# TDA7292_Amplifier.net
KiCad netlist of a schematic drawn in Altium Designer
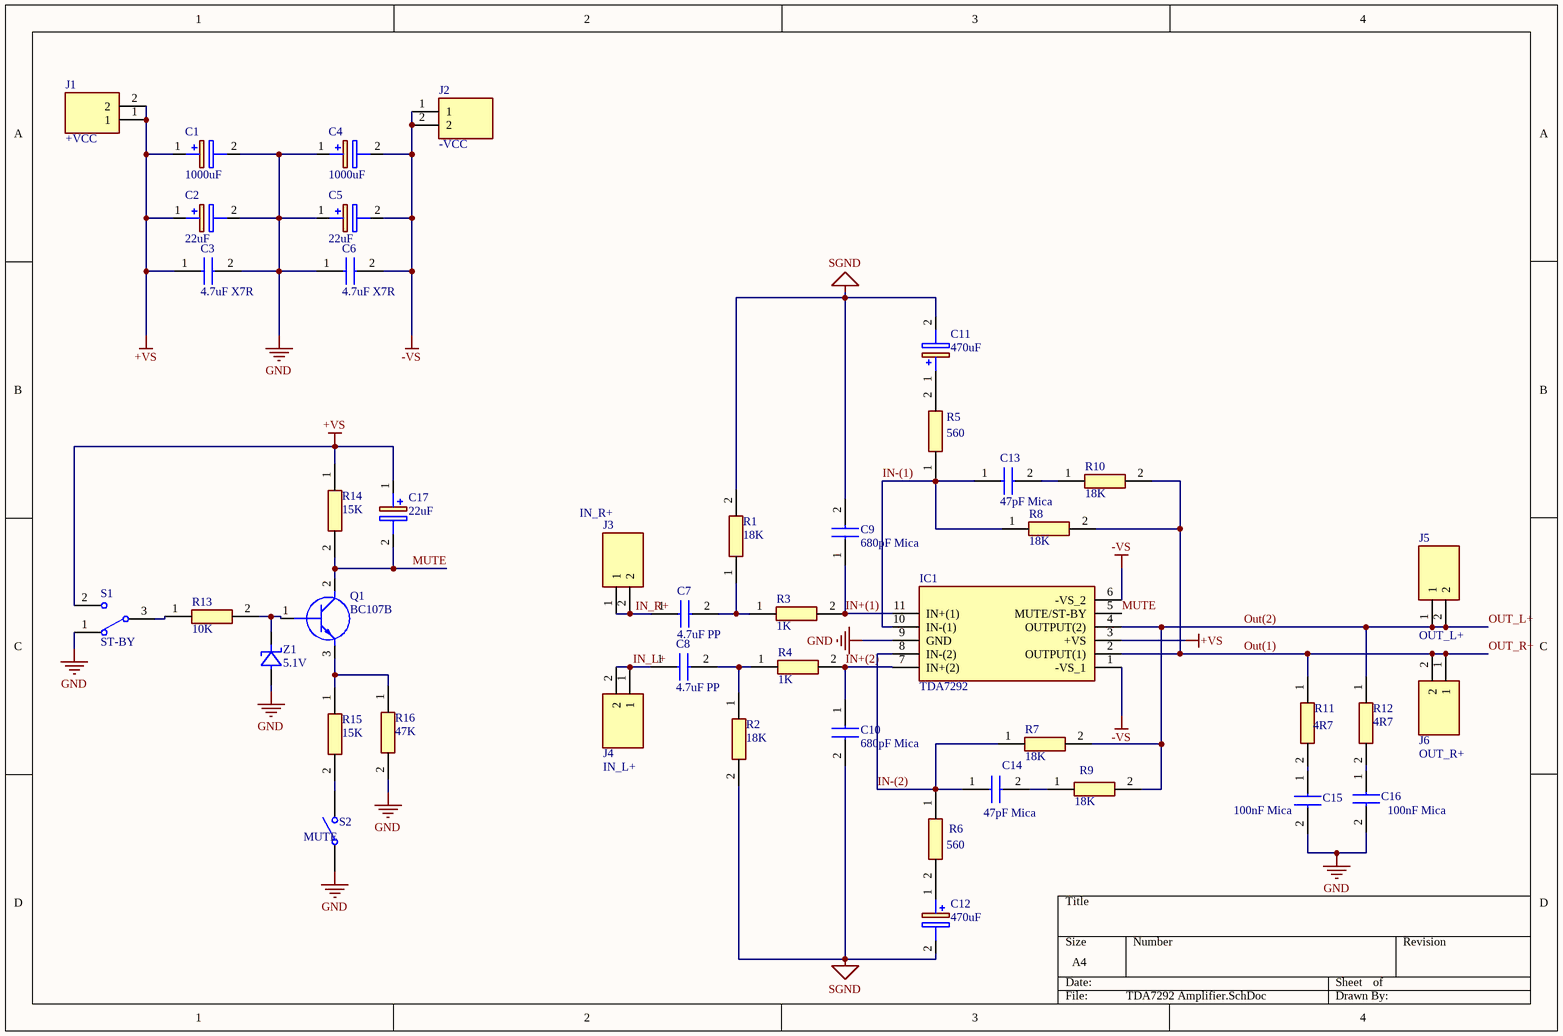
[diagram p0: TDA7292 Amplifier.SchDoc]

(export (version "E")
  (design (tool "Eeschema 10.0.6"))
  (components
    (comp (ref "C1")
      (value "1000uF")
      (footprint "Capacitor 1000uF")
      (description "Electroletic Capacitor Polarised")
      (fields
        (field (name "MANUFACTURER_PART_NUMBER") "UHE1H102MHD6TN")
        (field (name "MOUSER PART NUMBER") "647-UHE1H102MHD6TN")
      )
      (libsource (lib "TDA7292 Amplifier") (part "1000uF"))
    )
    (comp (ref "C2")
      (value "22uF")
      (footprint "Capacitor 22uF")
      (description "Electroletic Capacitor Polarised")
      (fields
        (field (name "MANUFACTURER_PART_NUMBER") "EEU-FM1H220")
        (field (name "MOUSER PART NUMBER") "667-EEU-FM1H220")
      )
      (libsource (lib "") (part "22uF_1"))
    )
    (comp (ref "C3")
      (value "4.7uF X7R")
      (footprint "Capacitor 4.7UF 50V X7R")
      (description "Capacitor 4.7UF 50V X7R")
      (fields
        (field (name "MANUFACTURER_PART_NUMBER") "RCER71H475K3M1H03A")
        (field (name "MOUSER PART NUMBER") "81-RCER71H475K3M1H3A")
      )
      (libsource (lib "TDA7292 Amplifier") (part "4.7uF X7R"))
    )
    (comp (ref "C4")
      (value "1000uF")
      (footprint "Capacitor 1000uF")
      (description "Electroletic Capacitor Polarised")
      (fields
        (field (name "MANUFACTURER_PART_NUMBER") "UHE1H102MHD6TN")
        (field (name "MOUSER PART NUMBER") "647-UHE1H102MHD6TN")
      )
      (libsource (lib "TDA7292 Amplifier") (part "1000uF"))
    )
    (comp (ref "C5")
      (value "22uF")
      (footprint "Capacitor 22uF")
      (description "Electroletic Capacitor Polarised")
      (fields
        (field (name "MANUFACTURER_PART_NUMBER") "EEU-FM1H220")
        (field (name "MOUSER PART NUMBER") "667-EEU-FM1H220")
      )
      (libsource (lib "") (part "22uF_1"))
    )
    (comp (ref "C6")
      (value "4.7uF X7R")
      (footprint "Capacitor 4.7UF 50V X7R")
      (description "Capacitor 4.7UF 50V X7R")
      (fields
        (field (name "MANUFACTURER_PART_NUMBER") "RCER71H475K3M1H03A")
        (field (name "MOUSER PART NUMBER") "81-RCER71H475K3M1H3A")
      )
      (libsource (lib "TDA7292 Amplifier") (part "4.7uF X7R"))
    )
    (comp (ref "C7")
      (value "4.7uF PP")
      (footprint "4.7UF Polypropylene")
      (description "Cap Film 4.7uF 450VDC PP 5% (25.3 X 11.7 X 16.4mm) Radial 22.5mm 110C Bulk")
      (fields
        (field (name "MANUFACTURER") "Panasonic")
        (field (name "MANUFACTURER PART NUMBER") "ECW-FD2W475J")
      )
      (libsource (lib "TDA7292 Amplifier") (part "4.7uF PP"))
    )
    (comp (ref "C8")
      (value "4.7uF PP")
      (footprint "4.7UF Polypropylene")
      (description "Cap Film 4.7uF 450VDC PP 5% (25.3 X 11.7 X 16.4mm) Radial 22.5mm 110C Bulk")
      (fields
        (field (name "MANUFACTURER") "Panasonic")
        (field (name "MANUFACTURER PART NUMBER") "ECW-FD2W475J")
      )
      (libsource (lib "TDA7292 Amplifier") (part "4.7uF PP"))
    )
    (comp (ref "C9")
      (value "680pF Mica")
      (footprint "680pF Mica")
      (description "Capacitor 680pF Mica")
      (fields
        (field (name "MANUFACTURER_PART_NUMBER") "CD15FD221FO3F")
        (field (name "MOUSER PART NUMBER") "598-CD15FD221FO3F")
      )
      (libsource (lib "TDA7292 Amplifier") (part "680pF Mica"))
    )
    (comp (ref "C10")
      (value "680pF Mica")
      (footprint "680pF Mica")
      (description "Capacitor 680pF Mica")
      (fields
        (field (name "MANUFACTURER_PART_NUMBER") "CD15FD221FO3F")
        (field (name "MOUSER PART NUMBER") "598-CD15FD221FO3F")
      )
      (libsource (lib "TDA7292 Amplifier") (part "680pF Mica"))
    )
    (comp (ref "C11")
      (value "470uF")
      (footprint "Capacitor 470uF")
      (description "Electroletic Capacitor Polarised")
      (fields
        (field (name "MANUFACTURER_PART_NUMBER") "EEUFM1H471")
        (field (name "RS PART NUMBER") "5261698P")
      )
      (libsource (lib "TDA7292 Amplifier") (part "470uF"))
    )
    (comp (ref "C12")
      (value "470uF")
      (footprint "Capacitor 470uF")
      (description "Electroletic Capacitor Polarised")
      (fields
        (field (name "MANUFACTURER_PART_NUMBER") "EEUFM1H471")
        (field (name "RS PART NUMBER") "5261698P")
      )
      (libsource (lib "") (part "470uF_1"))
    )
    (comp (ref "C13")
      (value "47pF Mica")
      (footprint "47pF Mica")
      (description "Capacitor 47pF Mica")
      (fields
        (field (name "MANUFACTURER_PART_NUMBER") "CD15FD221FO3F")
        (field (name "MOUSER PART NUMBER") "598-CD15FD221FO3F")
      )
      (libsource (lib "TDA7292 Amplifier") (part "47pF Mica"))
    )
    (comp (ref "C14")
      (value "47pF Mica")
      (footprint "47pF Mica")
      (description "Capacitor 47pF Mica")
      (fields
        (field (name "MANUFACTURER_PART_NUMBER") "CD15FD221FO3F")
        (field (name "MOUSER PART NUMBER") "598-CD15FD221FO3F")
      )
      (libsource (lib "TDA7292 Amplifier") (part "47pF Mica"))
    )
    (comp (ref "C15")
      (value "100nF Mica")
      (footprint "680pF Mica")
      (description "Capacitor 680pF Mica")
      (fields
        (field (name "MANUFACTURER_PART_NUMBER") "CD15FD221FO3F")
        (field (name "MOUSER PART NUMBER") "598-CD15FD221FO3F")
      )
      (libsource (lib "TDA7292 Amplifier") (part "680pF Mica"))
    )
    (comp (ref "C16")
      (value "100nF Mica")
      (footprint "680pF Mica")
      (description "Capacitor 680pF Mica")
      (fields
        (field (name "MANUFACTURER_PART_NUMBER") "CD15FD221FO3F")
        (field (name "MOUSER PART NUMBER") "598-CD15FD221FO3F")
      )
      (libsource (lib "TDA7292 Amplifier") (part "680pF Mica"))
    )
    (comp (ref "C17")
      (value "22uF")
      (footprint "Capacitor 22uF")
      (description "Electroletic Capacitor Polarised")
      (fields
        (field (name "MANUFACTURER_PART_NUMBER") "EEU-FM1H220")
        (field (name "MOUSER PART NUMBER") "667-EEU-FM1H220")
      )
      (libsource (lib "TDA7292 Amplifier") (part "22uF"))
    )
    (comp (ref "IC1")
      (value "TDA7292")
      (footprint "TDA7292")
      (description "Integrated Circuit")
      (fields (field (name "MOUSER PART NUMBER") "511-TDA7292"))
      (libsource (lib "TDA7292 Amplifier") (part "TDA7292"))
    )
    (comp (ref "J1")
      (value "+VCC")
      (footprint "Spade Terminals")
      (description "Connector")
      (fields
        (field (name "MANUFACTURER_PART_NUMBER") "725964-2")
        (field (name "MOUSER PART NUMBER") "571-725964-2")
      )
      (libsource (lib "") (part "Spade Terminals_1"))
    )
    (comp (ref "J2")
      (value "-VCC")
      (footprint "Spade Terminals")
      (description "Connector")
      (fields
        (field (name "MANUFACTURER_PART_NUMBER") "725964-2")
        (field (name "MOUSER PART NUMBER") "571-725964-2")
      )
      (libsource (lib "") (part "Spade Terminals_3"))
    )
    (comp (ref "J3")
      (value "IN_R+")
      (footprint "Spade Terminals")
      (description "Connector")
      (fields
        (field (name "MANUFACTURER_PART_NUMBER") "725964-2")
        (field (name "MOUSER PART NUMBER") "571-725964-2")
      )
      (libsource (lib "") (part "Spade Terminals_2"))
    )
    (comp (ref "J4")
      (value "IN_L+")
      (footprint "Spade Terminals")
      (description "Connector")
      (fields
        (field (name "MANUFACTURER_PART_NUMBER") "725964-2")
        (field (name "MOUSER PART NUMBER") "571-725964-2")
      )
      (libsource (lib "TDA7292 Amplifier") (part "Spade Terminals"))
    )
    (comp (ref "J5")
      (value "OUT_L+")
      (footprint "Spade Terminals")
      (description "Connector")
      (fields
        (field (name "MANUFACTURER_PART_NUMBER") "725964-2")
        (field (name "MOUSER PART NUMBER") "571-725964-2")
      )
      (libsource (lib "") (part "Spade Terminals_2"))
    )
    (comp (ref "J6")
      (value "OUT_R+")
      (footprint "Spade Terminals")
      (description "Connector")
      (fields
        (field (name "MANUFACTURER_PART_NUMBER") "725964-2")
        (field (name "MOUSER PART NUMBER") "571-725964-2")
      )
      (libsource (lib "TDA7292 Amplifier") (part "Spade Terminals"))
    )
    (comp (ref "Q1")
      (value "BC107B")
      (footprint "TDA7292 Amplifier:TO-18")
      (description "Transistor BJT NPN")
      (fields (field (name "MOUSER PART NUMBER") "511-BC107B") (field (name "RS PART NUMBER") "7140489P"))
      (libsource (lib "TDA7292 Amplifier") (part "BC107B"))
    )
    (comp (ref "R1")
      (value "18K")
      (footprint "RES 1/4W")
      (description "Resistor")
      (fields
        (field (name "MANUFACTURER_PART_NUMBER") "CFR-25JT-52-1K")
        (field (name "MOUSER PART NUMBER") "603-CFR-25JT-52-1K")
      )
      (libsource (lib "") (part "Resistor 1/4W_2"))
    )
    (comp (ref "R2")
      (value "18K")
      (footprint "RES 1/4W")
      (description "Resistor")
      (fields
        (field (name "MANUFACTURER_PART_NUMBER") "CFR-25JT-52-1K")
        (field (name "MOUSER PART NUMBER") "603-CFR-25JT-52-1K")
      )
      (libsource (lib "") (part "Resistor 1/4W_1"))
    )
    (comp (ref "R3")
      (value "1K")
      (footprint "RES 1/4W")
      (description "Resistor")
      (fields
        (field (name "MANUFACTURER_PART_NUMBER") "CFR-25JT-52-1K")
        (field (name "MOUSER PART NUMBER") "603-CFR-25JT-52-1K")
      )
      (libsource (lib "TDA7292 Amplifier") (part "Resistor 1/4W"))
    )
    (comp (ref "R4")
      (value "1K")
      (footprint "RES 1/4W")
      (description "Resistor")
      (fields
        (field (name "MANUFACTURER_PART_NUMBER") "CFR-25JT-52-1K")
        (field (name "MOUSER PART NUMBER") "603-CFR-25JT-52-1K")
      )
      (libsource (lib "TDA7292 Amplifier") (part "Resistor 1/4W"))
    )
    (comp (ref "R5")
      (value "560")
      (footprint "RES 1/4W")
      (description "Resistor")
      (fields
        (field (name "MANUFACTURER_PART_NUMBER") "CFR-25JT-52-1K")
        (field (name "MOUSER PART NUMBER") "603-CFR-25JT-52-1K")
      )
      (libsource (lib "") (part "Resistor 1/4W_2"))
    )
    (comp (ref "R6")
      (value "560")
      (footprint "RES 1/4W")
      (description "Resistor")
      (fields
        (field (name "MANUFACTURER_PART_NUMBER") "CFR-25JT-52-1K")
        (field (name "MOUSER PART NUMBER") "603-CFR-25JT-52-1K")
      )
      (libsource (lib "") (part "Resistor 1/4W_1"))
    )
    (comp (ref "R7")
      (value "18K")
      (footprint "RES 1/4W")
      (description "Resistor")
      (fields
        (field (name "MANUFACTURER_PART_NUMBER") "CFR-25JT-52-1K")
        (field (name "MOUSER PART NUMBER") "603-CFR-25JT-52-1K")
      )
      (libsource (lib "TDA7292 Amplifier") (part "Resistor 1/4W"))
    )
    (comp (ref "R8")
      (value "18K")
      (footprint "RES 1/4W")
      (description "Resistor")
      (fields
        (field (name "MANUFACTURER_PART_NUMBER") "CFR-25JT-52-1K")
        (field (name "MOUSER PART NUMBER") "603-CFR-25JT-52-1K")
      )
      (libsource (lib "TDA7292 Amplifier") (part "Resistor 1/4W"))
    )
    (comp (ref "R9")
      (value "18K")
      (footprint "RES 1/4W")
      (description "Resistor")
      (fields
        (field (name "MANUFACTURER_PART_NUMBER") "CFR-25JT-52-1K")
        (field (name "MOUSER PART NUMBER") "603-CFR-25JT-52-1K")
      )
      (libsource (lib "TDA7292 Amplifier") (part "Resistor 1/4W"))
    )
    (comp (ref "R10")
      (value "18K")
      (footprint "RES 1/4W")
      (description "Resistor")
      (fields
        (field (name "MANUFACTURER_PART_NUMBER") "CFR-25JT-52-1K")
        (field (name "MOUSER PART NUMBER") "603-CFR-25JT-52-1K")
      )
      (libsource (lib "TDA7292 Amplifier") (part "Resistor 1/4W"))
    )
    (comp (ref "R11")
      (value "4R7")
      (footprint "RES 1W")
      (description "Resistor 1W")
      (fields
        (field (name "MANUFACTURER_PART_NUMBER") "OM2405E-R58")
        (field (name "MOUSER PART NUMBER") "588-OM2405E-R58")
      )
      (libsource (lib "TDA7292 Amplifier") (part "Resistor 1W"))
    )
    (comp (ref "R12")
      (value "4R7")
      (footprint "RES 1W")
      (description "Resistor 1W")
      (fields
        (field (name "MANUFACTURER_PART_NUMBER") "OM2405E-R58")
        (field (name "MOUSER PART NUMBER") "588-OM2405E-R58")
      )
      (libsource (lib "TDA7292 Amplifier") (part "Resistor 1W"))
    )
    (comp (ref "R13")
      (value "10K")
      (footprint "RES 1/4W")
      (description "Resistor")
      (fields
        (field (name "MANUFACTURER_PART_NUMBER") "CFR-25JT-52-1K")
        (field (name "MOUSER PART NUMBER") "603-CFR-25JT-52-1K")
      )
      (libsource (lib "TDA7292 Amplifier") (part "Resistor 1/4W"))
    )
    (comp (ref "R14")
      (value "15K")
      (footprint "RES 1/4W")
      (description "Resistor")
      (fields
        (field (name "MANUFACTURER_PART_NUMBER") "CFR-25JT-52-1K")
        (field (name "MOUSER PART NUMBER") "603-CFR-25JT-52-1K")
      )
      (libsource (lib "") (part "Resistor 1/4W_1"))
    )
    (comp (ref "R15")
      (value "15K")
      (footprint "RES 1/4W")
      (description "Resistor")
      (fields
        (field (name "MANUFACTURER_PART_NUMBER") "CFR-25JT-52-1K")
        (field (name "MOUSER PART NUMBER") "603-CFR-25JT-52-1K")
      )
      (libsource (lib "") (part "Resistor 1/4W_1"))
    )
    (comp (ref "R16")
      (value "47K")
      (footprint "RES 1/4W")
      (description "Resistor")
      (fields
        (field (name "MANUFACTURER_PART_NUMBER") "CFR-25JT-52-1K")
        (field (name "MOUSER PART NUMBER") "603-CFR-25JT-52-1K")
      )
      (libsource (lib "") (part "Resistor 1/4W_1"))
    )
    (comp (ref "S1")
      (value "ST-BY")
      (footprint "SPDT")
      (description "SPDT Subminiature Toggle Switch, Right Angle Mounting, Vertical Actuation")
      (fields (field (name "PUBLISHER") "Altium Limited"))
      (libsource (lib "TDA7292 Amplifier") (part "SW-SPDT"))
    )
    (comp (ref "S2")
      (value "MUTE")
      (footprint "SPST")
      (description "Single-Pole, Single-Throw Switch")
      (fields (field (name "PUBLISHER") "Altium Limited"))
      (libsource (lib "TDA7292 Amplifier") (part "SW-SPST"))
    )
    (comp (ref "Z1")
      (value "5.1V")
      (footprint "DO-35 Zener")
      (description "Zener Diode 5.1V")
      (fields
        (field (name "MANUFACTURER_PART_NUMBER") "BZX55C5V1-TAP")
        (field (name "COPYRIGHT") "Copyright (C) 2018 Accelerated Designs. All rights reserved")
      )
      (libsource (lib "TDA7292 Amplifier") (part "Zener"))
    )
  )
  (nets
    (net (code "1") (name "+VS") (class "Default")
      (node (ref "C1") (pin "1") (pinfunction "+_1") (pintype "passive"))
      (node (ref "C17") (pin "1") (pinfunction "+_1") (pintype "passive"))
      (node (ref "C2") (pin "1") (pinfunction "+_1") (pintype "passive"))
      (node (ref "C3") (pin "1") (pinfunction "1_1") (pintype "passive"))
      (node (ref "IC1") (pin "3") (pinfunction "+VS_3") (pintype "passive"))
      (node (ref "J1") (pin "1") (pinfunction "1_1") (pintype "passive"))
      (node (ref "J1") (pin "2") (pinfunction "2_2") (pintype "passive"))
      (node (ref "R14") (pin "1") (pinfunction "1_1") (pintype "passive"))
      (node (ref "S1") (pin "2") (pinfunction "2_2") (pintype "passive"))
    )
    (net (code "2") (name "-VS") (class "Default")
      (node (ref "C4") (pin "2") (pinfunction "-_2") (pintype "passive"))
      (node (ref "C5") (pin "2") (pinfunction "-_2") (pintype "passive"))
      (node (ref "C6") (pin "2") (pinfunction "2_2") (pintype "passive"))
      (node (ref "IC1") (pin "1") (pinfunction "-VS_1_1") (pintype "passive"))
      (node (ref "IC1") (pin "6") (pinfunction "-VS_2_6") (pintype "passive"))
      (node (ref "J2") (pin "1") (pinfunction "1_1") (pintype "passive"))
      (node (ref "J2") (pin "2") (pinfunction "2_2") (pintype "passive"))
    )
    (net (code "3") (name "/IN+(1)") (class "Default")
      (node (ref "C9") (pin "1") (pinfunction "1_1") (pintype "passive"))
      (node (ref "IC1") (pin "11") (pinfunction "IN+(1)_11") (pintype "passive"))
      (node (ref "R3") (pin "2") (pinfunction "2_2") (pintype "passive"))
    )
    (net (code "4") (name "/IN+(2)") (class "Default")
      (node (ref "C10") (pin "1") (pinfunction "1_1") (pintype "passive"))
      (node (ref "IC1") (pin "7") (pinfunction "IN+(2)_7") (pintype "passive"))
      (node (ref "R4") (pin "2") (pinfunction "2_2") (pintype "passive"))
    )
    (net (code "5") (name "/IN-(1)") (class "Default")
      (node (ref "C13") (pin "1") (pinfunction "1_1") (pintype "passive"))
      (node (ref "IC1") (pin "10") (pinfunction "IN-(1)_10") (pintype "passive"))
      (node (ref "R5") (pin "1") (pinfunction "1_1") (pintype "passive"))
      (node (ref "R8") (pin "1") (pinfunction "1_1") (pintype "passive"))
    )
    (net (code "6") (name "/IN-(2)") (class "Default")
      (node (ref "C14") (pin "1") (pinfunction "1_1") (pintype "passive"))
      (node (ref "IC1") (pin "8") (pinfunction "IN-(2)_8") (pintype "passive"))
      (node (ref "R6") (pin "1") (pinfunction "1_1") (pintype "passive"))
      (node (ref "R7") (pin "1") (pinfunction "1_1") (pintype "passive"))
    )
    (net (code "7") (name "/IN_L+") (class "Default")
      (node (ref "C8") (pin "1") (pinfunction "1_1") (pintype "passive"))
      (node (ref "J4") (pin "1") (pinfunction "1_1") (pintype "passive"))
      (node (ref "J4") (pin "2") (pinfunction "2_2") (pintype "passive"))
    )
    (net (code "8") (name "/IN_R+") (class "Default")
      (node (ref "C7") (pin "1") (pinfunction "1_1") (pintype "passive"))
      (node (ref "J3") (pin "1") (pinfunction "1_1") (pintype "passive"))
      (node (ref "J3") (pin "2") (pinfunction "2_2") (pintype "passive"))
    )
    (net (code "9") (name "/MUTE") (class "Default")
      (node (ref "C17") (pin "2") (pinfunction "-_2") (pintype "passive"))
      (node (ref "IC1") (pin "5") (pinfunction "MUTE/ST-BY_5") (pintype "passive"))
      (node (ref "Q1") (pin "2") (pinfunction "C_2") (pintype "passive"))
      (node (ref "R14") (pin "2") (pinfunction "2_2") (pintype "passive"))
    )
    (net (code "10") (name "/OUT_L+") (class "Default")
      (node (ref "IC1") (pin "4") (pinfunction "OUTPUT(2)_4") (pintype "passive"))
      (node (ref "J5") (pin "1") (pinfunction "1_1") (pintype "passive"))
      (node (ref "J5") (pin "2") (pinfunction "2_2") (pintype "passive"))
      (node (ref "R12") (pin "1") (pinfunction "1_1") (pintype "passive"))
      (node (ref "R7") (pin "2") (pinfunction "2_2") (pintype "passive"))
      (node (ref "R9") (pin "2") (pinfunction "2_2") (pintype "passive"))
    )
    (net (code "11") (name "/OUT_R+") (class "Default")
      (node (ref "IC1") (pin "2") (pinfunction "OUTPUT(1)_2") (pintype "passive"))
      (node (ref "J6") (pin "1") (pinfunction "1_1") (pintype "passive"))
      (node (ref "J6") (pin "2") (pinfunction "2_2") (pintype "passive"))
      (node (ref "R10") (pin "2") (pinfunction "2_2") (pintype "passive"))
      (node (ref "R11") (pin "1") (pinfunction "1_1") (pintype "passive"))
      (node (ref "R8") (pin "2") (pinfunction "2_2") (pintype "passive"))
    )
    (net (code "12") (name "GND") (class "Default")
      (node (ref "C1") (pin "2") (pinfunction "-_2") (pintype "passive"))
      (node (ref "C15") (pin "2") (pinfunction "2_2") (pintype "passive"))
      (node (ref "C16") (pin "2") (pinfunction "2_2") (pintype "passive"))
      (node (ref "C2") (pin "2") (pinfunction "-_2") (pintype "passive"))
      (node (ref "C3") (pin "2") (pinfunction "2_2") (pintype "passive"))
      (node (ref "C4") (pin "1") (pinfunction "+_1") (pintype "passive"))
      (node (ref "C5") (pin "1") (pinfunction "+_1") (pintype "passive"))
      (node (ref "C6") (pin "1") (pinfunction "1_1") (pintype "passive"))
      (node (ref "IC1") (pin "9") (pinfunction "GND_9") (pintype "passive"))
      (node (ref "R16") (pin "2") (pinfunction "2_2") (pintype "passive"))
      (node (ref "S1") (pin "1") (pinfunction "1_1") (pintype "passive"))
      (node (ref "S2") (pin "1") (pinfunction "COMMON_1") (pintype "passive"))
      (node (ref "Z1") (pin "2") (pinfunction "2_2") (pintype "passive"))
    )
    (net (code "13") (name "Net-(C7-Pad2)") (class "Default")
      (node (ref "C7") (pin "2") (pinfunction "2_2") (pintype "passive"))
      (node (ref "R1") (pin "1") (pinfunction "1_1") (pintype "passive"))
      (node (ref "R3") (pin "1") (pinfunction "1_1") (pintype "passive"))
    )
    (net (code "14") (name "Net-(C8-Pad2)") (class "Default")
      (node (ref "C8") (pin "2") (pinfunction "2_2") (pintype "passive"))
      (node (ref "R2") (pin "1") (pinfunction "1_1") (pintype "passive"))
      (node (ref "R4") (pin "1") (pinfunction "1_1") (pintype "passive"))
    )
    (net (code "15") (name "Net-(C11-+)") (class "Default")
      (node (ref "C11") (pin "1") (pinfunction "+_1") (pintype "passive"))
      (node (ref "R5") (pin "2") (pinfunction "2_2") (pintype "passive"))
    )
    (net (code "16") (name "Net-(C12-+)") (class "Default")
      (node (ref "C12") (pin "1") (pinfunction "+_1") (pintype "passive"))
      (node (ref "R6") (pin "2") (pinfunction "2_2") (pintype "passive"))
    )
    (net (code "17") (name "Net-(C13-Pad2)") (class "Default")
      (node (ref "C13") (pin "2") (pinfunction "2_2") (pintype "passive"))
      (node (ref "R10") (pin "1") (pinfunction "1_1") (pintype "passive"))
    )
    (net (code "18") (name "Net-(C14-Pad2)") (class "Default")
      (node (ref "C14") (pin "2") (pinfunction "2_2") (pintype "passive"))
      (node (ref "R9") (pin "1") (pinfunction "1_1") (pintype "passive"))
    )
    (net (code "19") (name "Net-(C15-Pad1)") (class "Default")
      (node (ref "C15") (pin "1") (pinfunction "1_1") (pintype "passive"))
      (node (ref "R11") (pin "2") (pinfunction "2_2") (pintype "passive"))
    )
    (net (code "20") (name "Net-(C16-Pad1)") (class "Default")
      (node (ref "C16") (pin "1") (pinfunction "1_1") (pintype "passive"))
      (node (ref "R12") (pin "2") (pinfunction "2_2") (pintype "passive"))
    )
    (net (code "21") (name "Net-(Q1-B)") (class "Default")
      (node (ref "Q1") (pin "1") (pinfunction "B_1") (pintype "passive"))
      (node (ref "R13") (pin "2") (pinfunction "2_2") (pintype "passive"))
      (node (ref "Z1") (pin "1") (pinfunction "1_1") (pintype "passive"))
    )
    (net (code "22") (name "Net-(Q1-E)") (class "Default")
      (node (ref "Q1") (pin "3") (pinfunction "E_3") (pintype "passive"))
      (node (ref "R15") (pin "1") (pinfunction "1_1") (pintype "passive"))
      (node (ref "R16") (pin "1") (pinfunction "1_1") (pintype "passive"))
    )
    (net (code "23") (name "Net-(R13-Pad1)") (class "Default")
      (node (ref "R13") (pin "1") (pinfunction "1_1") (pintype "passive"))
      (node (ref "S1") (pin "3") (pinfunction "3_3") (pintype "passive"))
    )
    (net (code "24") (name "Net-(S2-NO)") (class "Default")
      (node (ref "R15") (pin "2") (pinfunction "2_2") (pintype "passive"))
      (node (ref "S2") (pin "2") (pinfunction "NO_2") (pintype "passive"))
    )
    (net (code "25") (name "SGND") (class "Default")
      (node (ref "C10") (pin "2") (pinfunction "2_2") (pintype "passive"))
      (node (ref "C11") (pin "2") (pinfunction "-_2") (pintype "passive"))
      (node (ref "C12") (pin "2") (pinfunction "-_2") (pintype "passive"))
      (node (ref "C9") (pin "2") (pinfunction "2_2") (pintype "passive"))
      (node (ref "R1") (pin "2") (pinfunction "2_2") (pintype "passive"))
      (node (ref "R2") (pin "2") (pinfunction "2_2") (pintype "passive"))
    )
  )
)
